# millionOhms.net
KiCad netlist of a schematic drawn in EAGLE
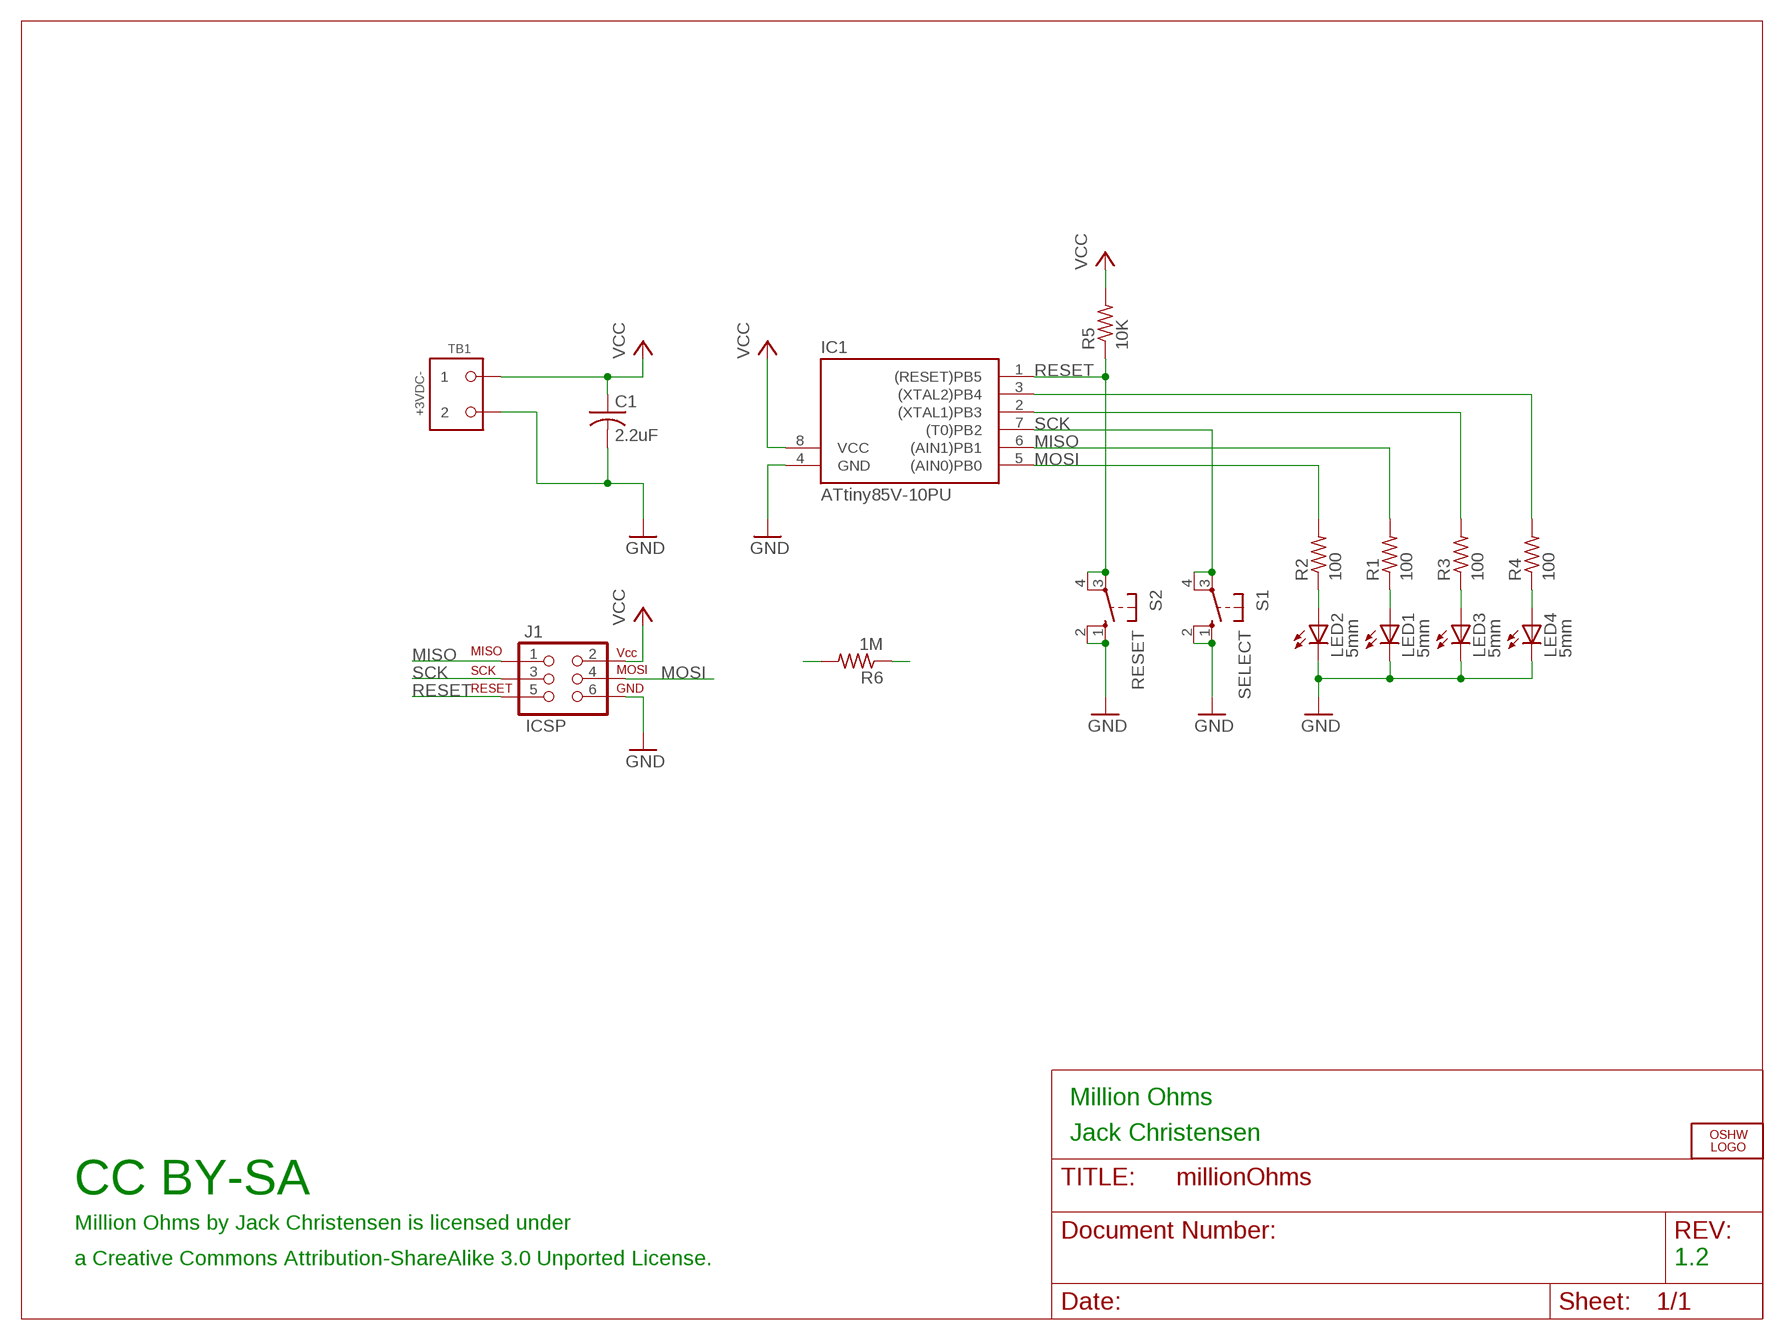
[diagram p0: schematic, sheet 1]

(export (version "E")
  (design (tool "Eeschema 10.0.6"))
  (components
    (comp (ref "C1")
      (value "2.2uF")
      (footprint "eagle-import:C025-025X050")
      (libsource (lib "eagle-import") (part "C-US025-025X050"))
    )
    (comp (ref "IC1")
      (value "ATtiny85V-10PU")
      (footprint "eagle-import:DIL08")
      (libsource (lib "eagle-import") (part "TINY10P"))
    )
    (comp (ref "J1")
      (value "ICSP")
      (footprint "eagle-import:2X3")
      (libsource (lib "eagle-import") (part "AVR_SPI_PRG_6PTH"))
    )
    (comp (ref "LED1")
      (value "5mm")
      (footprint "eagle-import:LED5MM")
      (libsource (lib "eagle-import") (part "LED5MM"))
    )
    (comp (ref "LED2")
      (value "5mm")
      (footprint "eagle-import:LED5MM")
      (libsource (lib "eagle-import") (part "LED5MM"))
    )
    (comp (ref "LED3")
      (value "5mm")
      (footprint "eagle-import:LED5MM")
      (libsource (lib "eagle-import") (part "LED5MM"))
    )
    (comp (ref "LED4")
      (value "5mm")
      (footprint "eagle-import:LED5MM")
      (libsource (lib "eagle-import") (part "LED5MM"))
    )
    (comp (ref "LOGO2")
      (value "OSHW_LOGO_8MILX0150-NT")
      (footprint "eagle-import:OSHW_8X150_NOTEXT")
      (libsource (lib "eagle-import") (part "OSHW_LOGO_8MILX0150-NT"))
    )
    (comp (ref "R1")
      (value "100")
      (footprint "eagle-import:0204_6")
      (libsource (lib "eagle-import") (part "R-US_0204/6"))
    )
    (comp (ref "R2")
      (value "100")
      (footprint "eagle-import:0204_6")
      (libsource (lib "eagle-import") (part "R-US_0204/6"))
    )
    (comp (ref "R3")
      (value "100")
      (footprint "eagle-import:0204_6")
      (libsource (lib "eagle-import") (part "R-US_0204/6"))
    )
    (comp (ref "R4")
      (value "100")
      (footprint "eagle-import:0204_6")
      (libsource (lib "eagle-import") (part "R-US_0204/6"))
    )
    (comp (ref "R5")
      (value "10K")
      (footprint "eagle-import:0204_6")
      (libsource (lib "eagle-import") (part "R-US_0204/6"))
    )
    (comp (ref "R6")
      (value "1M")
      (footprint "eagle-import:5616_20")
      (libsource (lib "eagle-import") (part "R-US_5616/20"))
    )
    (comp (ref "S1")
      (value "SELECT")
      (footprint "eagle-import:B3F-10XXOCT")
      (libsource (lib "eagle-import") (part "10-XXOCT"))
    )
    (comp (ref "S2")
      (value "RESET")
      (footprint "eagle-import:B3F-10XXOCT")
      (libsource (lib "eagle-import") (part "10-XXOCT"))
    )
    (comp (ref "TB1")
      (value "+3VDC-")
      (footprint "eagle-import:OST-TB-2-3.5MM")
      (libsource (lib "eagle-import") (part "OST-TB-23.5MM"))
    )
  )
  (nets
    (net (code "1") (name "/MISO") (class "Default")
      (node (ref "IC1") (pin "6") (pinfunction "(AIN1)PB1_6") (pintype "bidirectional"))
      (node (ref "J1") (pin "1") (pinfunction "1_1") (pintype "passive"))
      (node (ref "R1") (pin "2") (pinfunction "2_2") (pintype "passive"))
    )
    (net (code "2") (name "/MOSI") (class "Default")
      (node (ref "IC1") (pin "5") (pinfunction "(AIN0)PB0_5") (pintype "bidirectional"))
      (node (ref "J1") (pin "4") (pinfunction "4_4") (pintype "passive"))
      (node (ref "R2") (pin "2") (pinfunction "2_2") (pintype "passive"))
    )
    (net (code "3") (name "/RESET") (class "Default")
      (node (ref "IC1") (pin "1") (pinfunction "(RESET)PB5_1") (pintype "bidirectional"))
      (node (ref "J1") (pin "5") (pinfunction "5_5") (pintype "passive"))
      (node (ref "R5") (pin "1") (pinfunction "1_1") (pintype "passive"))
      (node (ref "S2") (pin "3") (pinfunction "P_3") (pintype "passive"))
      (node (ref "S2") (pin "4") (pinfunction "P1_4") (pintype "passive"))
    )
    (net (code "4") (name "/SCK") (class "Default")
      (node (ref "IC1") (pin "7") (pinfunction "(T0)PB2_7") (pintype "bidirectional"))
      (node (ref "J1") (pin "3") (pinfunction "3_3") (pintype "passive"))
      (node (ref "S1") (pin "3") (pinfunction "P_3") (pintype "passive"))
      (node (ref "S1") (pin "4") (pinfunction "P1_4") (pintype "passive"))
    )
    (net (code "5") (name "GND") (class "Default")
      (node (ref "C1") (pin "2") (pinfunction "2_2") (pintype "passive"))
      (node (ref "IC1") (pin "4") (pinfunction "GND_4") (pintype "power_in"))
      (node (ref "J1") (pin "6") (pinfunction "6_6") (pintype "passive"))
      (node (ref "LED1") (pin "K") (pinfunction "C_K") (pintype "passive"))
      (node (ref "LED2") (pin "K") (pinfunction "C_K") (pintype "passive"))
      (node (ref "LED3") (pin "K") (pinfunction "C_K") (pintype "passive"))
      (node (ref "LED4") (pin "K") (pinfunction "C_K") (pintype "passive"))
      (node (ref "S1") (pin "1") (pinfunction "S_1") (pintype "passive"))
      (node (ref "S1") (pin "2") (pinfunction "S1_2") (pintype "passive"))
      (node (ref "S2") (pin "1") (pinfunction "S_1") (pintype "passive"))
      (node (ref "S2") (pin "2") (pinfunction "S1_2") (pintype "passive"))
      (node (ref "TB1") (pin "P$2") (pinfunction "2_P$2") (pintype "passive"))
    )
    (net (code "6") (name "Net-(IC1-(XTAL1)PB3)") (class "Default")
      (node (ref "IC1") (pin "2") (pinfunction "(XTAL1)PB3_2") (pintype "bidirectional"))
      (node (ref "R3") (pin "2") (pinfunction "2_2") (pintype "passive"))
    )
    (net (code "7") (name "Net-(IC1-(XTAL2)PB4)") (class "Default")
      (node (ref "IC1") (pin "3") (pinfunction "(XTAL2)PB4_3") (pintype "bidirectional"))
      (node (ref "R4") (pin "2") (pinfunction "2_2") (pintype "passive"))
    )
    (net (code "8") (name "Net-(LED1-PadA)") (class "Default")
      (node (ref "LED1") (pin "A") (pinfunction "A_A") (pintype "passive"))
      (node (ref "R1") (pin "1") (pinfunction "1_1") (pintype "passive"))
    )
    (net (code "9") (name "Net-(LED2-PadA)") (class "Default")
      (node (ref "LED2") (pin "A") (pinfunction "A_A") (pintype "passive"))
      (node (ref "R2") (pin "1") (pinfunction "1_1") (pintype "passive"))
    )
    (net (code "10") (name "Net-(LED3-PadA)") (class "Default")
      (node (ref "LED3") (pin "A") (pinfunction "A_A") (pintype "passive"))
      (node (ref "R3") (pin "1") (pinfunction "1_1") (pintype "passive"))
    )
    (net (code "11") (name "Net-(LED4-PadA)") (class "Default")
      (node (ref "LED4") (pin "A") (pinfunction "A_A") (pintype "passive"))
      (node (ref "R4") (pin "1") (pinfunction "1_1") (pintype "passive"))
    )
    (net (code "12") (name "VCC") (class "Default")
      (node (ref "C1") (pin "1") (pinfunction "1_1") (pintype "passive"))
      (node (ref "IC1") (pin "8") (pinfunction "VCC_8") (pintype "power_in"))
      (node (ref "J1") (pin "2") (pinfunction "2_2") (pintype "passive"))
      (node (ref "R5") (pin "2") (pinfunction "2_2") (pintype "passive"))
      (node (ref "TB1") (pin "P$1") (pinfunction "1_P$1") (pintype "passive"))
    )
    (net (code "13") (name "unconnected-(R6-1-PadP$1)") (class "Default")
      (node (ref "R6") (pin "P$1") (pinfunction "1_P$1") (pintype "passive"))
    )
    (net (code "14") (name "unconnected-(R6-2-PadP$2)") (class "Default")
      (node (ref "R6") (pin "P$2") (pinfunction "2_P$2") (pintype "passive"))
    )
  )
)
